# lab2_arhipov_buck.net
KiCad netlist of a schematic drawn in Altium Designer
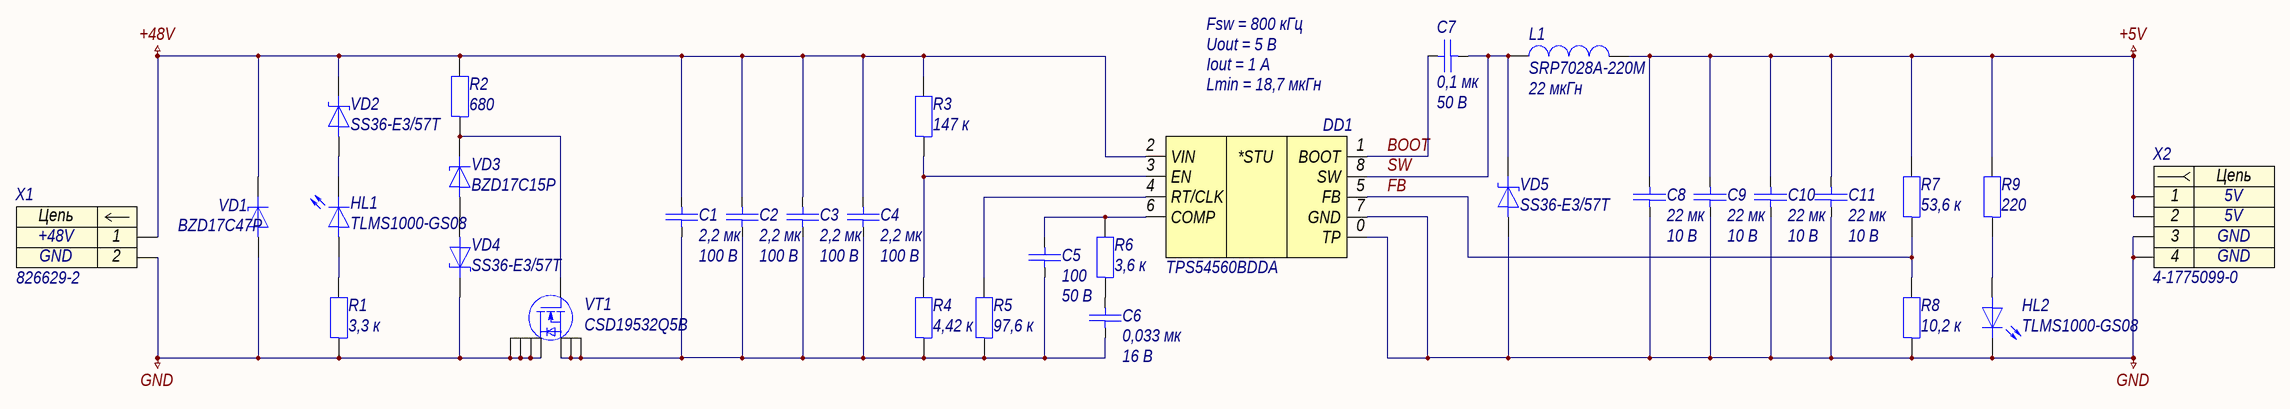
[diagram p0: lab2_arhipov_buck.SchDoc]

(export (version "E")
  (design (tool "Eeschema 10.0.6"))
  (components
    (comp (ref "C1")
      (value "2,2 мк")
      (footprint "C1206")
      (description "=Описание")
      (fields (field (name "НАПРЯЖЕНИЕ") "100 В"))
      (libsource (lib "Database_Students") (part "C-NONPOLAR"))
    )
    (comp (ref "C2")
      (value "2,2 мк")
      (footprint "C1206")
      (description "=Описание")
      (fields (field (name "НАПРЯЖЕНИЕ") "100 В"))
      (libsource (lib "Database_Students") (part "C-NONPOLAR"))
    )
    (comp (ref "C3")
      (value "2,2 мк")
      (footprint "C1206")
      (description "=Описание")
      (fields (field (name "НАПРЯЖЕНИЕ") "100 В"))
      (libsource (lib "Database_Students") (part "C-NONPOLAR"))
    )
    (comp (ref "C4")
      (value "2,2 мк")
      (footprint "C1206")
      (description "=Описание")
      (fields (field (name "НАПРЯЖЕНИЕ") "100 В"))
      (libsource (lib "Database_Students") (part "C-NONPOLAR"))
    )
    (comp (ref "C5")
      (value "100")
      (footprint "C0603")
      (description "=Описание")
      (fields (field (name "НАПРЯЖЕНИЕ") "50 В"))
      (libsource (lib "Database_Students") (part "C-NONPOLAR"))
    )
    (comp (ref "C6")
      (value "0,033 мк")
      (footprint "C0603")
      (description "=Описание")
      (fields (field (name "НАПРЯЖЕНИЕ") "16 В"))
      (libsource (lib "Database_Students") (part "C-NONPOLAR"))
    )
    (comp (ref "C7")
      (value "0,1 мк")
      (footprint "C0603")
      (description "=Описание")
      (fields (field (name "НАПРЯЖЕНИЕ") "50 В"))
      (libsource (lib "Database_Students") (part "C-NONPOLAR"))
    )
    (comp (ref "C8")
      (value "22 мк")
      (footprint "C0603")
      (description "=Описание")
      (fields (field (name "НАПРЯЖЕНИЕ") "10 В"))
      (libsource (lib "Database_Students") (part "C-NONPOLAR"))
    )
    (comp (ref "C9")
      (value "22 мк")
      (footprint "C0603")
      (description "=Описание")
      (fields (field (name "НАПРЯЖЕНИЕ") "10 В"))
      (libsource (lib "Database_Students") (part "C-NONPOLAR"))
    )
    (comp (ref "C10")
      (value "22 мк")
      (footprint "C0603")
      (description "=Описание")
      (fields (field (name "НАПРЯЖЕНИЕ") "10 В"))
      (libsource (lib "Database_Students") (part "C-NONPOLAR"))
    )
    (comp (ref "C11")
      (value "22 мк")
      (footprint "C0603")
      (description "=Описание")
      (fields (field (name "НАПРЯЖЕНИЕ") "10 В"))
      (libsource (lib "Database_Students") (part "C-NONPOLAR"))
    )
    (comp (ref "DD1")
      (value "TPS54560BDDA")
      (footprint "HSOP-8")
      (description "=Описание")
      (libsource (lib "Database_Students") (part "TPS54560BDDA"))
    )
    (comp (ref "HL1")
      (value "TLMS1000-GS08")
      (footprint "HL0603")
      (description "=Описание")
      (libsource (lib "Database_Students") (part "HL-COMMON"))
    )
    (comp (ref "HL2")
      (value "TLMS1000-GS08")
      (footprint "HL0603")
      (description "=Описание")
      (libsource (lib "Database_Students") (part "HL-COMMON"))
    )
    (comp (ref "L1")
      (value "SRP7028A-220M")
      (footprint "SRP-2-670X660X280")
      (description "=Описание")
      (fields (field (name "ИНДУКТИВНОСТЬ") "22 мкГн"))
      (libsource (lib "Database_Students") (part "INDUCTOR-COMMON"))
    )
    (comp (ref "R1")
      (value "3,3 к")
      (footprint "R0603")
      (description "=Описание")
      (libsource (lib "Database_Students") (part "R-COMMON"))
    )
    (comp (ref "R2")
      (value "680")
      (footprint "R0603")
      (description "=Описание")
      (libsource (lib "Database_Students") (part "R-COMMON"))
    )
    (comp (ref "R3")
      (value "147 к")
      (footprint "R0603")
      (description "=Описание")
      (libsource (lib "Database_Students") (part "R-COMMON"))
    )
    (comp (ref "R4")
      (value "4,42 к")
      (footprint "R0603")
      (description "=Описание")
      (libsource (lib "Database_Students") (part "R-COMMON"))
    )
    (comp (ref "R5")
      (value "97,6 к")
      (footprint "R0603")
      (description "=Описание")
      (libsource (lib "Database_Students") (part "R-COMMON"))
    )
    (comp (ref "R6")
      (value "3,6 к")
      (footprint "R0603")
      (description "=Описание")
      (libsource (lib "Database_Students") (part "R-COMMON"))
    )
    (comp (ref "R7")
      (value "53,6 к")
      (footprint "R0603")
      (description "=Описание")
      (libsource (lib "Database_Students") (part "R-COMMON"))
    )
    (comp (ref "R8")
      (value "10,2 к")
      (footprint "R0603")
      (description "=Описание")
      (libsource (lib "Database_Students") (part "R-COMMON"))
    )
    (comp (ref "R9")
      (value "220")
      (footprint "R0603")
      (description "=Описание")
      (libsource (lib "Database_Students") (part "R-COMMON"))
    )
    (comp (ref "VD1")
      (value "BZD17C47P")
      (footprint "DO-219AB")
      (description "=Описание")
      (libsource (lib "Database_Students") (part "ZENER-DIODE"))
    )
    (comp (ref "VD2")
      (value "SS36-E3/57T")
      (footprint "DO-214AB")
      (description "=Описание")
      (libsource (lib "Database_Students") (part "DIODE-SCHOTTKY"))
    )
    (comp (ref "VD3")
      (value "BZD17C15P")
      (footprint "DO-219AB")
      (description "=Описание")
      (libsource (lib "Database_Students") (part "ZENER-DIODE"))
    )
    (comp (ref "VD4")
      (value "SS36-E3/57T")
      (footprint "DO-214AB")
      (description "=Описание")
      (libsource (lib "Database_Students") (part "DIODE-SCHOTTKY"))
    )
    (comp (ref "VD5")
      (value "SS36-E3/57T")
      (footprint "DO-214AB")
      (description "=Описание")
      (libsource (lib "Database_Students") (part "DIODE-SCHOTTKY"))
    )
    (comp (ref "VT1")
      (value "CSD19532Q5B")
      (footprint "SON-8")
      (description "=Описание")
      (libsource (lib "Database_Students") (part "MOSFET-N-1G-3S-4D"))
    )
    (comp (ref "X1")
      (value "826629-2")
      (footprint "SnapEDApcb:TE_826629-2")
      (fields (field (name "MF") "TE Connectivity"))
      (libsource (lib "SnapEDAsch") (part "826629-2"))
    )
    (comp (ref "X2")
      (value "4-1775099-0")
      (footprint "4-1775099-0")
      (description "=Описание")
      (libsource (lib "Database_Students") (part "HEADER-4-SCT"))
    )
  )
  (nets
    (net (code "1") (name "+5V") (class "Default")
      (node (ref "C10") (pin "1") (pinfunction "1_1") (pintype "passive"))
      (node (ref "C11") (pin "1") (pinfunction "1_1") (pintype "passive"))
      (node (ref "C8") (pin "1") (pinfunction "1_1") (pintype "passive"))
      (node (ref "C9") (pin "1") (pinfunction "1_1") (pintype "passive"))
      (node (ref "L1") (pin "2") (pinfunction "2_2") (pintype "passive"))
      (node (ref "R7") (pin "2") (pinfunction "2_2") (pintype "passive"))
      (node (ref "R9") (pin "2") (pinfunction "2_2") (pintype "passive"))
      (node (ref "X2") (pin "1") (pinfunction "1_1") (pintype "passive"))
      (node (ref "X2") (pin "2") (pinfunction "2_2") (pintype "passive"))
    )
    (net (code "2") (name "+48V") (class "Default")
      (node (ref "C1") (pin "1") (pinfunction "1_1") (pintype "passive"))
      (node (ref "C2") (pin "1") (pinfunction "1_1") (pintype "passive"))
      (node (ref "C3") (pin "1") (pinfunction "1_1") (pintype "passive"))
      (node (ref "C4") (pin "1") (pinfunction "1_1") (pintype "passive"))
      (node (ref "DD1") (pin "2") (pinfunction "VIN_2") (pintype "passive"))
      (node (ref "R2") (pin "2") (pinfunction "2_2") (pintype "passive"))
      (node (ref "R3") (pin "2") (pinfunction "2_2") (pintype "passive"))
      (node (ref "VD1") (pin "1") (pinfunction "1_1") (pintype "passive"))
      (node (ref "VD2") (pin "1") (pinfunction "1_1") (pintype "passive"))
      (node (ref "X1") (pin "1") (pinfunction "1_1") (pintype "passive"))
    )
    (net (code "3") (name "/BOOT") (class "Default")
      (node (ref "C7") (pin "1") (pinfunction "1_1") (pintype "passive"))
      (node (ref "DD1") (pin "1") (pinfunction "BOOT_1") (pintype "passive"))
    )
    (net (code "4") (name "/FB") (class "Default")
      (node (ref "DD1") (pin "5") (pinfunction "FB_5") (pintype "passive"))
      (node (ref "R7") (pin "1") (pinfunction "1_1") (pintype "passive"))
      (node (ref "R8") (pin "2") (pinfunction "2_2") (pintype "passive"))
    )
    (net (code "5") (name "/SW") (class "Default")
      (node (ref "C7") (pin "2") (pinfunction "2_2") (pintype "passive"))
      (node (ref "DD1") (pin "8") (pinfunction "SW_8") (pintype "passive"))
      (node (ref "L1") (pin "1") (pinfunction "1_1") (pintype "passive"))
      (node (ref "VD5") (pin "1") (pinfunction "1_1") (pintype "passive"))
    )
    (net (code "6") (name "GND") (class "Default")
      (node (ref "C10") (pin "2") (pinfunction "2_2") (pintype "passive"))
      (node (ref "C11") (pin "2") (pinfunction "2_2") (pintype "passive"))
      (node (ref "C8") (pin "2") (pinfunction "2_2") (pintype "passive"))
      (node (ref "C9") (pin "2") (pinfunction "2_2") (pintype "passive"))
      (node (ref "DD1") (pin "0") (pinfunction "TP_0") (pintype "passive"))
      (node (ref "DD1") (pin "7") (pinfunction "GND_7") (pintype "passive"))
      (node (ref "HL2") (pin "1") (pinfunction "1_1") (pintype "passive"))
      (node (ref "R1") (pin "1") (pinfunction "1_1") (pintype "passive"))
      (node (ref "R8") (pin "1") (pinfunction "1_1") (pintype "passive"))
      (node (ref "VD1") (pin "2") (pinfunction "2_2") (pintype "passive"))
      (node (ref "VD4") (pin "1") (pinfunction "1_1") (pintype "passive"))
      (node (ref "VD5") (pin "2") (pinfunction "2_2") (pintype "passive"))
      (node (ref "VT1") (pin "D") (pinfunction "D_D") (pintype "passive"))
      (node (ref "X1") (pin "2") (pinfunction "2_2") (pintype "passive"))
      (node (ref "X2") (pin "3") (pinfunction "3_3") (pintype "passive"))
      (node (ref "X2") (pin "4") (pinfunction "4_4") (pintype "passive"))
    )
    (net (code "7") (name "Net-(C1-Pad2)") (class "Default")
      (node (ref "C1") (pin "2") (pinfunction "2_2") (pintype "passive"))
      (node (ref "C2") (pin "2") (pinfunction "2_2") (pintype "passive"))
      (node (ref "C3") (pin "2") (pinfunction "2_2") (pintype "passive"))
      (node (ref "C4") (pin "2") (pinfunction "2_2") (pintype "passive"))
      (node (ref "C5") (pin "2") (pinfunction "2_2") (pintype "passive"))
      (node (ref "C6") (pin "2") (pinfunction "2_2") (pintype "passive"))
      (node (ref "R4") (pin "1") (pinfunction "1_1") (pintype "passive"))
      (node (ref "R5") (pin "1") (pinfunction "1_1") (pintype "passive"))
      (node (ref "VT1") (pin "S") (pinfunction "S_S") (pintype "passive"))
    )
    (net (code "8") (name "Net-(C6-Pad1)") (class "Default")
      (node (ref "C6") (pin "1") (pinfunction "1_1") (pintype "passive"))
      (node (ref "R6") (pin "1") (pinfunction "1_1") (pintype "passive"))
    )
    (net (code "9") (name "Net-(DD1-COMP)") (class "Default")
      (node (ref "C5") (pin "1") (pinfunction "1_1") (pintype "passive"))
      (node (ref "DD1") (pin "6") (pinfunction "COMP_6") (pintype "passive"))
      (node (ref "R6") (pin "2") (pinfunction "2_2") (pintype "passive"))
    )
    (net (code "10") (name "Net-(DD1-EN)") (class "Default")
      (node (ref "DD1") (pin "3") (pinfunction "EN_3") (pintype "passive"))
      (node (ref "R3") (pin "1") (pinfunction "1_1") (pintype "passive"))
      (node (ref "R4") (pin "2") (pinfunction "2_2") (pintype "passive"))
    )
    (net (code "11") (name "Net-(DD1-RT{slash}CLK)") (class "Default")
      (node (ref "DD1") (pin "4") (pinfunction "RT/CLK_4") (pintype "passive"))
      (node (ref "R5") (pin "2") (pinfunction "2_2") (pintype "passive"))
    )
    (net (code "12") (name "Net-(HL1-Pad1)") (class "Default")
      (node (ref "HL1") (pin "1") (pinfunction "1_1") (pintype "passive"))
      (node (ref "VD2") (pin "2") (pinfunction "2_2") (pintype "passive"))
    )
    (net (code "13") (name "Net-(HL1-Pad2)") (class "Default")
      (node (ref "HL1") (pin "2") (pinfunction "2_2") (pintype "passive"))
      (node (ref "R1") (pin "2") (pinfunction "2_2") (pintype "passive"))
    )
    (net (code "14") (name "Net-(HL2-Pad2)") (class "Default")
      (node (ref "HL2") (pin "2") (pinfunction "2_2") (pintype "passive"))
      (node (ref "R9") (pin "1") (pinfunction "1_1") (pintype "passive"))
    )
    (net (code "15") (name "Net-(R2-Pad1)") (class "Default")
      (node (ref "R2") (pin "1") (pinfunction "1_1") (pintype "passive"))
      (node (ref "VD3") (pin "1") (pinfunction "1_1") (pintype "passive"))
      (node (ref "VT1") (pin "G") (pinfunction "G_G") (pintype "passive"))
    )
    (net (code "16") (name "Net-(VD3-Pad2)") (class "Default")
      (node (ref "VD3") (pin "2") (pinfunction "2_2") (pintype "passive"))
      (node (ref "VD4") (pin "2") (pinfunction "2_2") (pintype "passive"))
    )
  )
)
